# Backflow_Current_Control_Unit_BCCU.net
KiCad netlist of a schematic drawn in Altium Designer
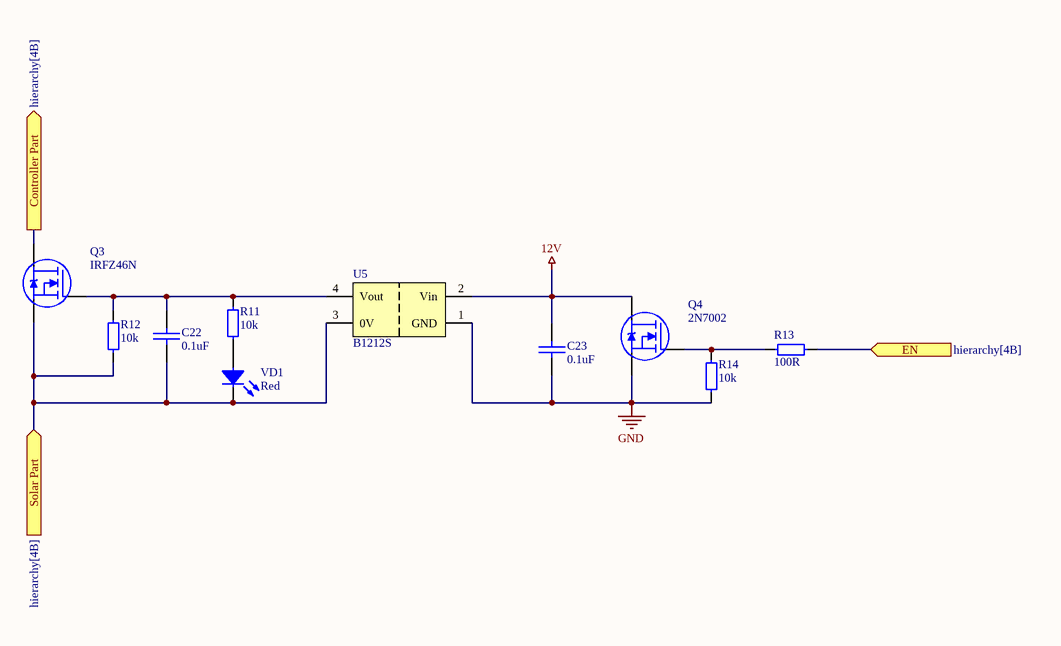
[diagram p0: Backflow Current Control Unit (BCCU).SchDoc]

(export (version "E")
  (design (tool "Eeschema 10.0.6"))
  (components
    (comp (ref "C22")
      (value "0.1uF")
      (footprint "0805 Capicator")
      (description "0.1uF X7R 25V 10% 0805")
      (fields
        (field (name "MANUFACTURER") "Murata Manufacturing")
        (field (name "PART NUMBER") "GRM21BR71E104KA01L")
      )
      (libsource (lib "BRT_Components") (part "Cap 0.1uF (0805)"))
    )
    (comp (ref "C23")
      (value "0.1uF")
      (footprint "0805 Capicator")
      (description "0.1uF X7R 25V 10% 0805")
      (fields
        (field (name "MANUFACTURER") "Murata Manufacturing")
        (field (name "PART NUMBER") "GRM21BR71E104KA01L")
      )
      (libsource (lib "BRT_Components") (part "Cap 0.1uF (0805)"))
    )
    (comp (ref "Q3")
      (value "IRFZ46N")
      (footprint "TO220")
      (description "MOSFT 55V 46A 16.5mOhm 48nC")
      (libsource (lib "Altium_Library") (part "MOSFET-N IRFZ46N"))
    )
    (comp (ref "Q4")
      (value "2N7002")
      (footprint "SOT23")
      (description "MOSFET-N 60V 0.3A 2Ohm")
      (libsource (lib "Altium_Library") (part "MOSFET-N 2N7002"))
    )
    (comp (ref "R11")
      (value "10k")
      (footprint "0805 Resistor")
      (description "0.125W 0805 10k, 1%")
      (fields (field (name "PART NUMBER") "RC0805FR-0710KL") (field (name "MANUFACTURER") "Taiwan"))
      (libsource (lib "BRT_Components") (part "Res 10k (0805)"))
    )
    (comp (ref "R12")
      (value "10k")
      (footprint "0805 Resistor")
      (description "0.125W 0805 10k, 1%")
      (fields (field (name "PART NUMBER") "RC0805FR-0710KL") (field (name "MANUFACTURER") "Taiwan"))
      (libsource (lib "BRT_Components") (part "Res 10k (0805)"))
    )
    (comp (ref "R13")
      (value "100R")
      (footprint "0805 Resistor")
      (description "0.125W 0805 100R, 1%")
      (fields (field (name "PART NUMBER") "RC0805FR-07100RL") (field (name "MANUFACTURER") "Taiwan"))
      (libsource (lib "BRT_Components") (part "Res 100R (0805)"))
    )
    (comp (ref "R14")
      (value "10k")
      (footprint "0805 Resistor")
      (description "0.125W 0805 10k, 1%")
      (fields (field (name "PART NUMBER") "RC0805FR-0710KL") (field (name "MANUFACTURER") "Taiwan"))
      (libsource (lib "BRT_Components") (part "Res 10k (0805)"))
    )
    (comp (ref "U5")
      (value "B1212S")
      (footprint "SIP4")
      (description "1W isolated DC-DC converter 12V-12V")
      (libsource (lib "Altium_Library") (part "DC/DC Isolated 12-12V B1212S-1WR3"))
    )
    (comp (ref "VD1")
      (value "Red")
      (footprint "LED: 0805R")
      (libsource (lib "Altium_Library") (part "LED Red 0805"))
    )
  )
  (nets
    (net (code "1") (name "/Controller Part") (class "Default")
      (node (ref "Q3") (pin "2") (pinfunction "Drain_2") (pintype "passive"))
    )
    (net (code "2") (name "/EN") (class "Default")
      (node (ref "R13") (pin "2") (pinfunction "2_2") (pintype "passive"))
    )
    (net (code "3") (name "/Solar Part") (class "Default")
      (node (ref "C22") (pin "1") (pinfunction "1_1") (pintype "passive"))
      (node (ref "Q3") (pin "3") (pinfunction "Source_3") (pintype "passive"))
      (node (ref "R12") (pin "2") (pinfunction "2_2") (pintype "passive"))
      (node (ref "U5") (pin "3") (pinfunction "0V_3") (pintype "passive"))
      (node (ref "VD1") (pin "2") (pinfunction "2_2") (pintype "passive"))
    )
    (net (code "4") (name "12V") (class "Default")
      (node (ref "C23") (pin "1") (pinfunction "1_1") (pintype "passive"))
      (node (ref "Q4") (pin "3") (pinfunction "Drain_3") (pintype "passive"))
      (node (ref "U5") (pin "2") (pinfunction "Vin_2") (pintype "passive"))
    )
    (net (code "5") (name "GND") (class "Default")
      (node (ref "C23") (pin "2") (pinfunction "2_2") (pintype "passive"))
      (node (ref "Q4") (pin "2") (pinfunction "Source_2") (pintype "passive"))
      (node (ref "R14") (pin "1") (pinfunction "1_1") (pintype "passive"))
      (node (ref "U5") (pin "1") (pinfunction "GND_1") (pintype "passive"))
    )
    (net (code "6") (name "Net-(Q3-Gate)") (class "Default")
      (node (ref "C22") (pin "2") (pinfunction "2_2") (pintype "passive"))
      (node (ref "Q3") (pin "1") (pinfunction "Gate_1") (pintype "passive"))
      (node (ref "R11") (pin "1") (pinfunction "1_1") (pintype "passive"))
      (node (ref "R12") (pin "1") (pinfunction "1_1") (pintype "passive"))
      (node (ref "U5") (pin "4") (pinfunction "Vout_4") (pintype "passive"))
    )
    (net (code "7") (name "Net-(Q4-Gate)") (class "Default")
      (node (ref "Q4") (pin "1") (pinfunction "Gate_1") (pintype "passive"))
      (node (ref "R13") (pin "1") (pinfunction "1_1") (pintype "passive"))
      (node (ref "R14") (pin "2") (pinfunction "2_2") (pintype "passive"))
    )
    (net (code "8") (name "Net-(R11-Pad2)") (class "Default")
      (node (ref "R11") (pin "2") (pinfunction "2_2") (pintype "passive"))
      (node (ref "VD1") (pin "1") (pinfunction "1_1") (pintype "passive"))
    )
  )
)
